# stm32_lora.net
KiCad netlist of a schematic drawn in EasyEDA Pro
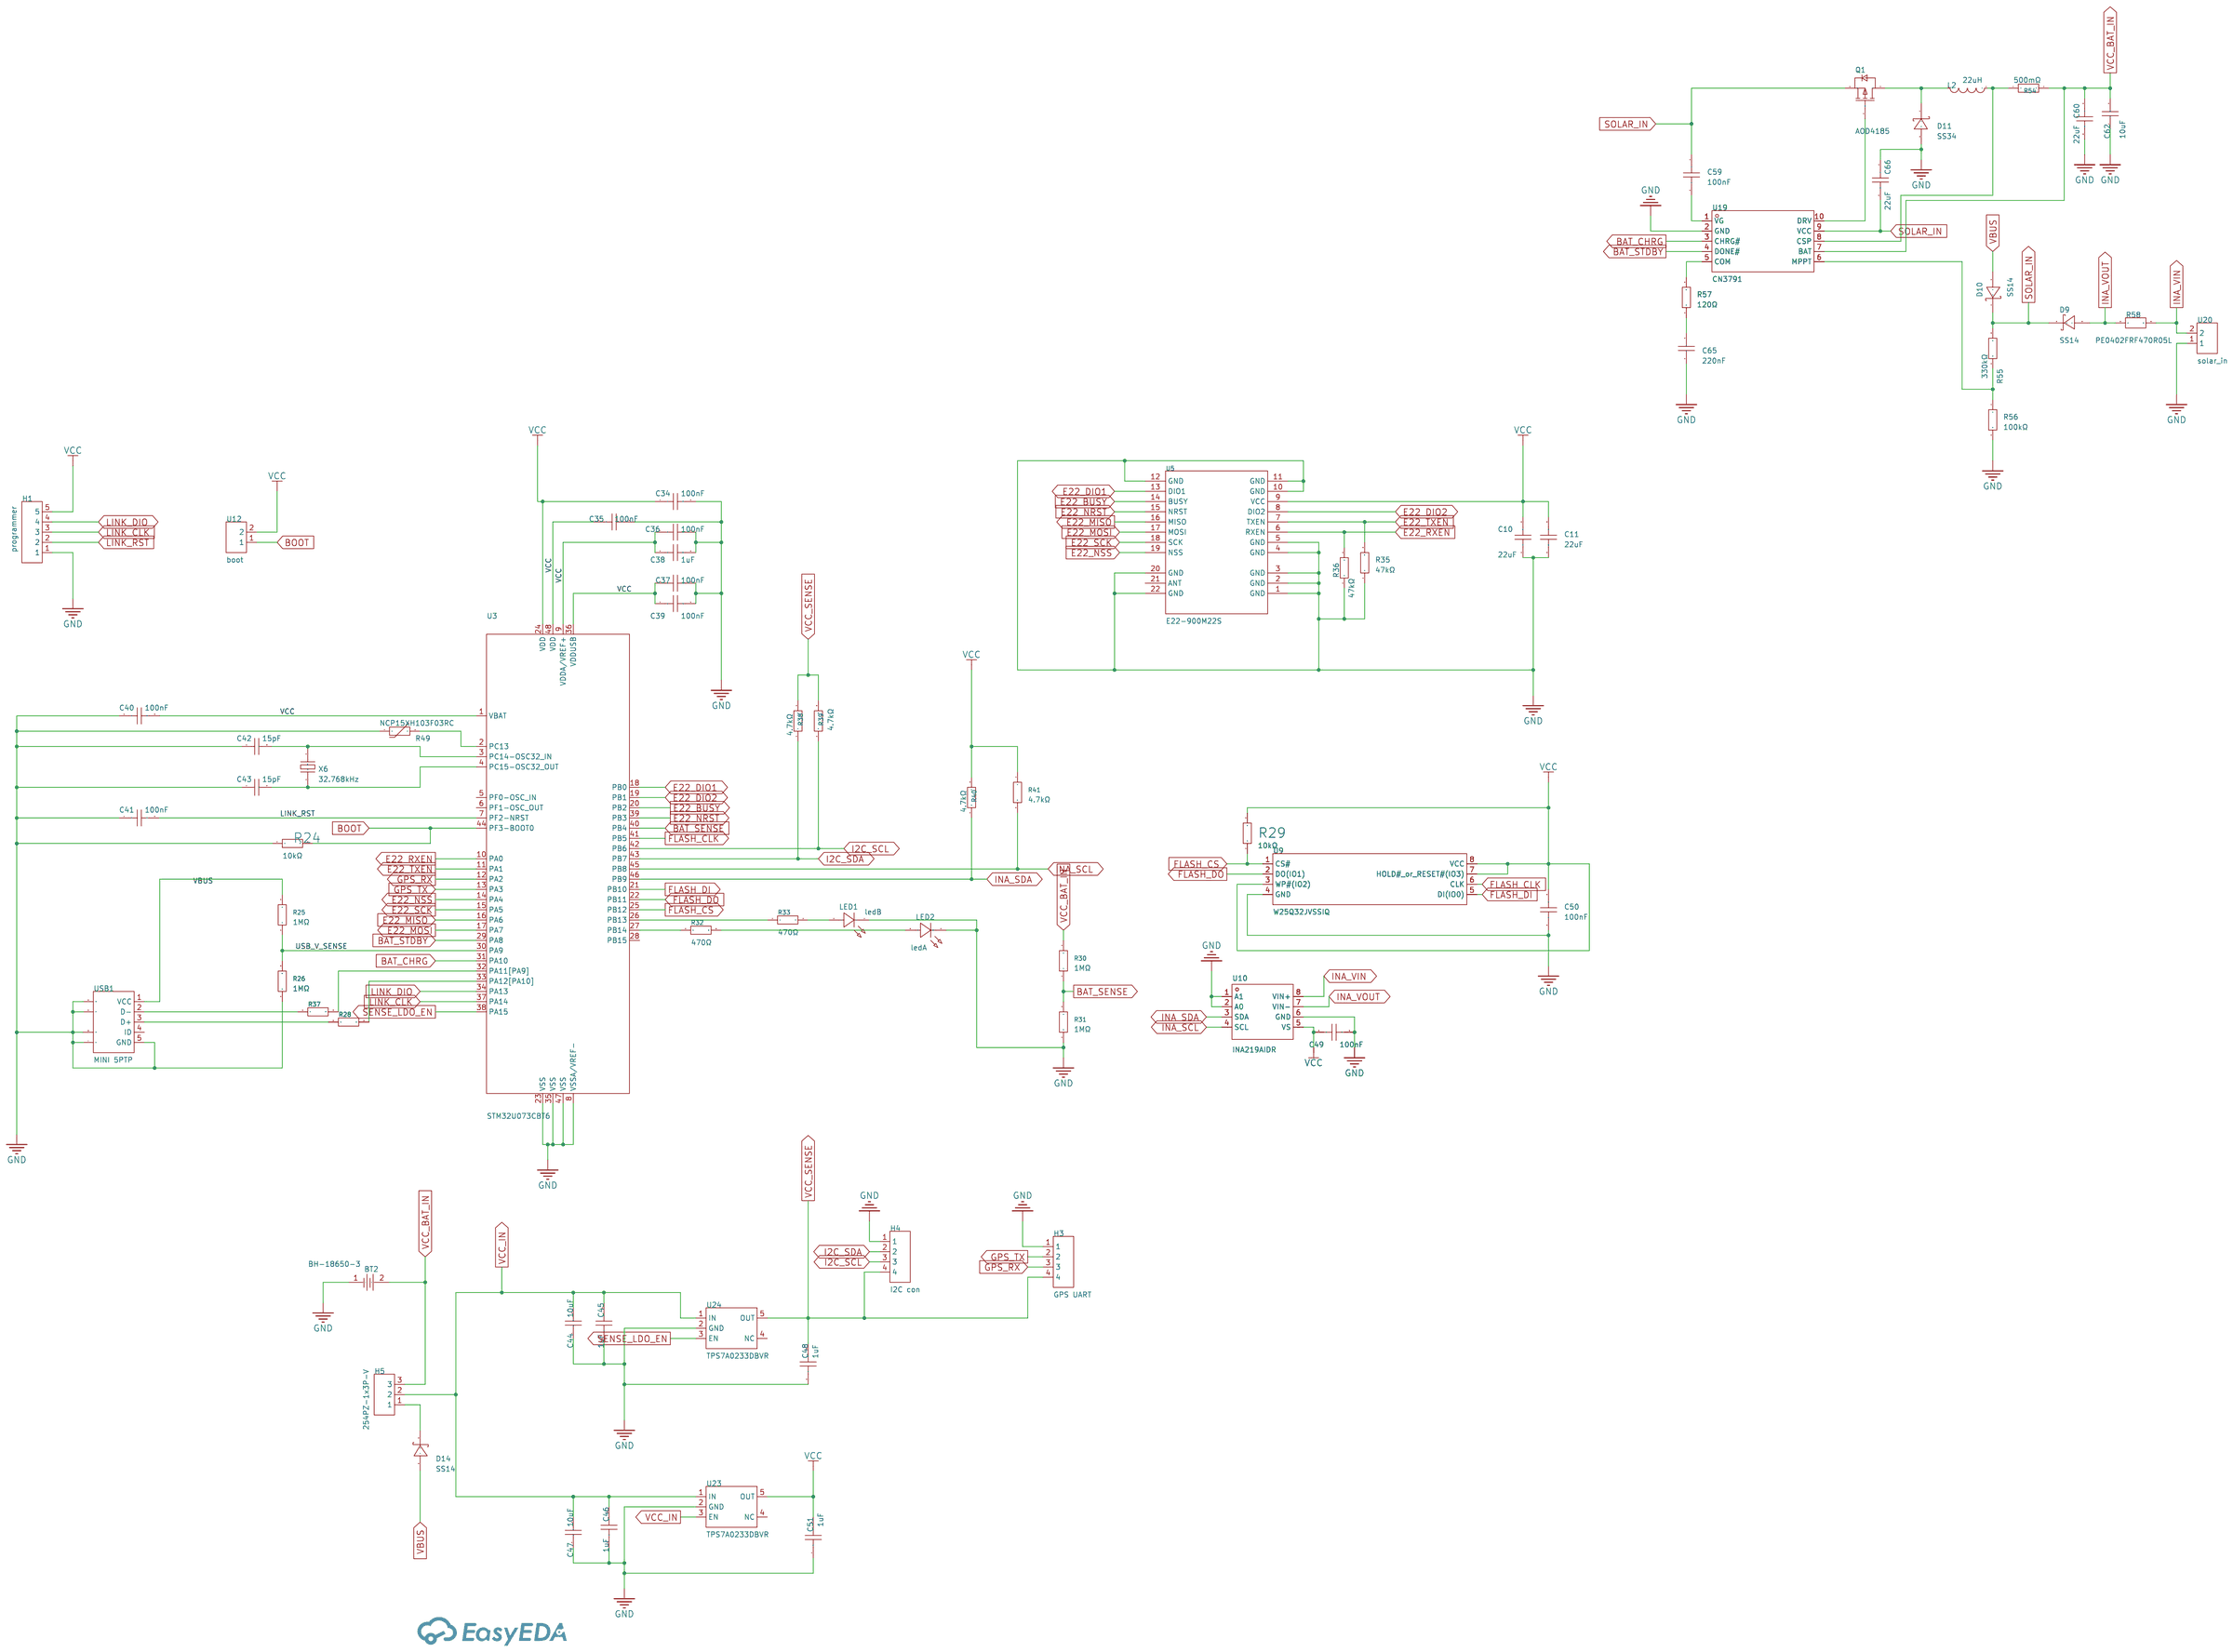
[diagram p0: schematic sheet]

(export (version "E")
  (design (tool "Eeschema 10.0.6"))
  (components
    (comp (ref "BT2")
      (value "BH-18650-3")
      (footprint "easyedapro:BAT-TH_BH-18650-3")
      (fields (field (name "Manufacturer") "HanElectricity(瀚源)"))
      (libsource (lib "easyedapro") (part "BH-18650-3"))
    )
    (comp (ref "C10")
      (value "22uF")
      (footprint "easyedapro:C0603")
      (description "Capacitance:22uF Tolerance:±20% Tolerance:±20% Voltage Rating:6.3V Temperature Coefficient:X5R")
      (fields
        (field (name "Manufacturer Part") "CL10A226MQ8NRNC")
        (field (name "Manufacturer") "SAMSUNG(三星)")
      )
      (libsource (lib "easyedapro") (part "CL10A226MQ8NRNC"))
    )
    (comp (ref "C11")
      (value "22uF")
      (footprint "easyedapro:C0603")
      (description "Capacitance:22uF Tolerance:±20% Tolerance:±20% Voltage Rating:6.3V Temperature Coefficient:X5R")
      (fields
        (field (name "Manufacturer Part") "CL10A226MQ8NRNC")
        (field (name "Manufacturer") "SAMSUNG(三星)")
      )
      (libsource (lib "easyedapro") (part "CL10A226MQ8NRNC"))
    )
    (comp (ref "C34")
      (value "100nF")
      (footprint "easyedapro:C0402")
      (description "Capacitance:100nF Tolerance:±10% Tolerance:±10% Voltage Rating:16V Temperature Coefficient:X7R")
      (fields
        (field (name "Manufacturer Part") "CL05B104KO5NNNC")
        (field (name "Manufacturer") "SAMSUNG(三星)")
      )
      (libsource (lib "easyedapro") (part "CL05B104KO5NNNC"))
    )
    (comp (ref "C35")
      (value "100nF")
      (footprint "easyedapro:C0402")
      (description "Capacitance:100nF Tolerance:±10% Tolerance:±10% Voltage Rating:16V Temperature Coefficient:X7R")
      (fields
        (field (name "Manufacturer Part") "CL05B104KO5NNNC")
        (field (name "Manufacturer") "SAMSUNG(三星)")
      )
      (libsource (lib "easyedapro") (part "CL05B104KO5NNNC"))
    )
    (comp (ref "C36")
      (value "100nF")
      (footprint "easyedapro:C0402")
      (description "Capacitance:100nF Tolerance:±10% Tolerance:±10% Voltage Rating:16V Temperature Coefficient:X7R")
      (fields
        (field (name "Manufacturer Part") "CL05B104KO5NNNC")
        (field (name "Manufacturer") "SAMSUNG(三星)")
      )
      (libsource (lib "easyedapro") (part "CL05B104KO5NNNC"))
    )
    (comp (ref "C37")
      (value "100nF")
      (footprint "easyedapro:C0402")
      (description "Capacitance:100nF Tolerance:±10% Tolerance:±10% Voltage Rating:16V Temperature Coefficient:X7R")
      (fields
        (field (name "Manufacturer Part") "CL05B104KO5NNNC")
        (field (name "Manufacturer") "SAMSUNG(三星)")
      )
      (libsource (lib "easyedapro") (part "CL05B104KO5NNNC"))
    )
    (comp (ref "C38")
      (value "1uF")
      (footprint "easyedapro:C0402")
      (description "Capacitance:1uF Tolerance:±10% Tolerance:±10% Voltage Rating:25V Temperature Coefficient:X5R")
      (fields
        (field (name "Manufacturer Part") "CL05A105KA5NQNC")
        (field (name "Manufacturer") "SAMSUNG(三星)")
      )
      (libsource (lib "easyedapro") (part "CL05A105KA5NQNC"))
    )
    (comp (ref "C39")
      (value "100nF")
      (footprint "easyedapro:C0402")
      (description "Capacitance:100nF Tolerance:±10% Tolerance:±10% Voltage Rating:16V Temperature Coefficient:X7R")
      (fields
        (field (name "Manufacturer Part") "CL05B104KO5NNNC")
        (field (name "Manufacturer") "SAMSUNG(三星)")
      )
      (libsource (lib "easyedapro") (part "CL05B104KO5NNNC"))
    )
    (comp (ref "C40")
      (value "100nF")
      (footprint "easyedapro:C0402")
      (description "Capacitance:100nF Tolerance:±10% Tolerance:±10% Voltage Rating:16V Temperature Coefficient:X7R")
      (fields
        (field (name "Manufacturer Part") "CL05B104KO5NNNC")
        (field (name "Manufacturer") "SAMSUNG(三星)")
      )
      (libsource (lib "easyedapro") (part "CL05B104KO5NNNC"))
    )
    (comp (ref "C41")
      (value "100nF")
      (footprint "easyedapro:C0402")
      (description "Capacitance:100nF Tolerance:±10% Tolerance:±10% Voltage Rating:16V Temperature Coefficient:X7R")
      (fields
        (field (name "Manufacturer Part") "CL05B104KO5NNNC")
        (field (name "Manufacturer") "SAMSUNG(三星)")
      )
      (libsource (lib "easyedapro") (part "CL05B104KO5NNNC"))
    )
    (comp (ref "C42")
      (value "15pF")
      (footprint "easyedapro:C0402")
      (description "Capacitance:15pF Tolerance:±5% Tolerance:±5% Voltage Rating:50V Temperature Coefficient:C0G")
      (fields (field (name "Manufacturer Part") "0402CG150J500NT") (field (name "Manufacturer") "FH(风华)"))
      (libsource (lib "easyedapro") (part "0402CG150J500NT"))
    )
    (comp (ref "C43")
      (value "15pF")
      (footprint "easyedapro:C0402")
      (description "Capacitance:15pF Tolerance:±5% Tolerance:±5% Voltage Rating:50V Temperature Coefficient:C0G")
      (fields (field (name "Manufacturer Part") "0402CG150J500NT") (field (name "Manufacturer") "FH(风华)"))
      (libsource (lib "easyedapro") (part "0402CG150J500NT"))
    )
    (comp (ref "C44")
      (value "10uF")
      (footprint "easyedapro:C0402")
      (description "Capacitance:10uF Tolerance:±20% Tolerance:±20% Voltage Rating:6.3V Temperature Coefficient:X5R")
      (fields
        (field (name "Manufacturer Part") "CL05A106MQ5NUNC")
        (field (name "Manufacturer") "SAMSUNG(三星)")
      )
      (libsource (lib "easyedapro") (part "CL05A106MQ5NUNC"))
    )
    (comp (ref "C45")
      (value "1uF")
      (footprint "easyedapro:C0402")
      (description "Capacitance:1uF Tolerance:±10% Tolerance:±10% Voltage Rating:25V Temperature Coefficient:X5R")
      (fields
        (field (name "Manufacturer Part") "CL05A105KA5NQNC")
        (field (name "Manufacturer") "SAMSUNG(三星)")
      )
      (libsource (lib "easyedapro") (part "CL05A105KA5NQNC"))
    )
    (comp (ref "C46")
      (value "1uF")
      (footprint "easyedapro:C0402")
      (description "Capacitance:1uF Tolerance:±10% Tolerance:±10% Voltage Rating:25V Temperature Coefficient:X5R")
      (fields
        (field (name "Manufacturer Part") "CL05A105KA5NQNC")
        (field (name "Manufacturer") "SAMSUNG(三星)")
      )
      (libsource (lib "easyedapro") (part "CL05A105KA5NQNC"))
    )
    (comp (ref "C47")
      (value "10uF")
      (footprint "easyedapro:C0402")
      (description "Capacitance:10uF Tolerance:±20% Tolerance:±20% Voltage Rating:6.3V Temperature Coefficient:X5R")
      (fields
        (field (name "Manufacturer Part") "CL05A106MQ5NUNC")
        (field (name "Manufacturer") "SAMSUNG(三星)")
      )
      (libsource (lib "easyedapro") (part "CL05A106MQ5NUNC"))
    )
    (comp (ref "C48")
      (value "1uF")
      (footprint "easyedapro:C0402")
      (description "Capacitance:1uF Tolerance:±10% Tolerance:±10% Voltage Rating:25V Temperature Coefficient:X5R")
      (fields
        (field (name "Manufacturer Part") "CL05A105KA5NQNC")
        (field (name "Manufacturer") "SAMSUNG(三星)")
      )
      (libsource (lib "easyedapro") (part "CL05A105KA5NQNC"))
    )
    (comp (ref "C49")
      (value "100nF")
      (footprint "easyedapro:C0402")
      (description "Capacitance:100nF Tolerance:±10% Tolerance:±10% Voltage Rating:16V Temperature Coefficient:X7R")
      (fields
        (field (name "Manufacturer Part") "CL05B104KO5NNNC")
        (field (name "Manufacturer") "SAMSUNG(三星)")
      )
      (libsource (lib "easyedapro") (part "CL05B104KO5NNNC"))
    )
    (comp (ref "C50")
      (value "100nF")
      (footprint "easyedapro:C0402")
      (description "Capacitance:100nF Tolerance:±10% Tolerance:±10% Voltage Rating:16V Temperature Coefficient:X7R")
      (fields
        (field (name "Manufacturer Part") "CL05B104KO5NNNC")
        (field (name "Manufacturer") "SAMSUNG(三星)")
      )
      (libsource (lib "easyedapro") (part "CL05B104KO5NNNC"))
    )
    (comp (ref "C51")
      (value "1uF")
      (footprint "easyedapro:C0402")
      (description "Capacitance:1uF Tolerance:±10% Tolerance:±10% Voltage Rating:25V Temperature Coefficient:X5R")
      (fields
        (field (name "Manufacturer Part") "CL05A105KA5NQNC")
        (field (name "Manufacturer") "SAMSUNG(三星)")
      )
      (libsource (lib "easyedapro") (part "CL05A105KA5NQNC"))
    )
    (comp (ref "C59")
      (value "100nF")
      (footprint "easyedapro:C0402")
      (description "Capacitance:100nF Tolerance:±10% Tolerance:±10% Voltage Rating:16V Temperature Coefficient:X7R")
      (fields
        (field (name "Manufacturer Part") "CL05B104KO5NNNC")
        (field (name "Manufacturer") "SAMSUNG(三星)")
      )
      (libsource (lib "easyedapro") (part "CL05B104KO5NNNC"))
    )
    (comp (ref "C60")
      (value "22uF")
      (footprint "easyedapro:C0603")
      (description "Capacitance:22uF Tolerance:±20% Tolerance:±20% Voltage Rating:6.3V Temperature Coefficient:X5R")
      (fields
        (field (name "Manufacturer Part") "CL10A226MQ8NRNC")
        (field (name "Manufacturer") "SAMSUNG(三星)")
      )
      (libsource (lib "easyedapro") (part "CL10A226MQ8NRNC"))
    )
    (comp (ref "C62")
      (value "10uF")
      (footprint "easyedapro:C0402")
      (description "Capacitance:10uF Tolerance:±20% Tolerance:±20% Voltage Rating:6.3V Temperature Coefficient:X5R")
      (fields
        (field (name "Manufacturer Part") "CL05A106MQ5NUNC")
        (field (name "Manufacturer") "SAMSUNG(三星)")
      )
      (libsource (lib "easyedapro") (part "CL05A106MQ5NUNC"))
    )
    (comp (ref "C65")
      (value "220nF")
      (footprint "easyedapro:C0402")
      (description "Capacitance:220nF Tolerance:±10% Tolerance:±10% Voltage Rating:16V Temperature Coefficient:X7R")
      (fields
        (field (name "Manufacturer Part") "CL05B224KO5NNNC")
        (field (name "Manufacturer") "SAMSUNG(三星)")
      )
      (libsource (lib "easyedapro") (part "CL05B224KO5NNNC"))
    )
    (comp (ref "C66")
      (value "22uF")
      (footprint "easyedapro:C0603")
      (description "Capacitance:22uF Tolerance:±20% Tolerance:±20% Voltage Rating:6.3V Temperature Coefficient:X5R")
      (fields
        (field (name "Manufacturer Part") "CL10A226MQ8NRNC")
        (field (name "Manufacturer") "SAMSUNG(三星)")
      )
      (libsource (lib "easyedapro") (part "CL10A226MQ8NRNC"))
    )
    (comp (ref "D9")
      (value "SS14")
      (footprint "easyedapro:SMA_L4.2-W2.6-LS5.0-RD_1")
      (fields (field (name "Manufacturer") "MDD(辰达半导体)"))
      (libsource (lib "easyedapro") (part "SS14"))
    )
    (comp (ref "D10")
      (value "SS14")
      (footprint "easyedapro:SMA_L4.2-W2.6-LS5.0-RD_1")
      (fields (field (name "Manufacturer") "MDD(辰达半导体)"))
      (libsource (lib "easyedapro") (part "SS14"))
    )
    (comp (ref "D11")
      (value "SS34")
      (footprint "easyedapro:SMA_L4.3-W2.6-LS5.2-RD")
      (fields (field (name "Manufacturer") "MDD(辰达半导体)"))
      (libsource (lib "easyedapro") (part "SS34_C8678"))
    )
    (comp (ref "D14")
      (value "SS14")
      (footprint "easyedapro:SMA_L4.2-W2.6-LS5.0-RD_1")
      (fields (field (name "Manufacturer") "MDD(辰达半导体)"))
      (libsource (lib "easyedapro") (part "SS14"))
    )
    (comp (ref "H1")
      (value "programmer")
      (footprint "easyedapro:HDR-TH_5P-P2.54-V-M")
      (fields (field (name "Manufacturer Part") "22284050") (field (name "Manufacturer") "MOLEX"))
      (libsource (lib "easyedapro") (part "22284050"))
    )
    (comp (ref "H3")
      (value "GPS UART")
      (footprint "easyedapro:HDR-TH_4P-HX-PH254-01-04-Z-L11.5")
      (fields
        (field (name "Manufacturer Part") "HX PH254-01-04-Z-L11.5 straight pin header")
        (field (name "Manufacturer") "hanxia(韩下)")
      )
      (libsource (lib "easyedapro") (part "HX PH254-01-04-Z-L11.5 STRAIGHT PIN HEADER"))
    )
    (comp (ref "H4")
      (value "I2C con")
      (footprint "easyedapro:HDR-TH_4P-HX-PH254-01-04-Z-L11.5")
      (fields
        (field (name "Manufacturer Part") "HX PH254-01-04-Z-L11.5 straight pin header")
        (field (name "Manufacturer") "hanxia(韩下)")
      )
      (libsource (lib "easyedapro") (part "HX PH254-01-04-Z-L11.5 STRAIGHT PIN HEADER"))
    )
    (comp (ref "H5")
      (value "254PZ-1x3P-V")
      (footprint "easyedapro:HDR-TH_3P-P2.54-V-M")
      (fields (field (name "Manufacturer") "LXWCONN(连兴旺电子)"))
      (libsource (lib "easyedapro") (part "254PZ-1X3P-V"))
    )
    (comp (ref "L2")
      (value "22uH")
      (footprint "easyedapro:IND-SMD_L4.0-W4.0_SLW4010S")
      (fields (field (name "Manufacturer Part") "SWPA4030S220MT") (field (name "Manufacturer") "Sunlord(顺络)"))
      (libsource (lib "easyedapro") (part "SWPA4030S220MT"))
    )
    (comp (ref "LED1")
      (value "ledB")
      (footprint "easyedapro:LED0603-RD")
      (fields
        (field (name "Manufacturer Part") "19-217/G7C-AM1N2B/6T")
        (field (name "Manufacturer") "EVERLIGHT(亿光)")
      )
      (libsource (lib "easyedapro") (part "19-217/G7C-AM1N2B/6T"))
    )
    (comp (ref "LED2")
      (value "ledA")
      (footprint "easyedapro:LED0603-RD")
      (fields
        (field (name "Manufacturer Part") "19-217/G7C-AM1N2B/6T")
        (field (name "Manufacturer") "EVERLIGHT(亿光)")
      )
      (libsource (lib "easyedapro") (part "19-217/G7C-AM1N2B/6T"))
    )
    (comp (ref "Q1")
      (value "AOD4185")
      (footprint "easyedapro:TO-252-3_L6.5-W5.8-P4.60-LS9.9-BR")
      (fields (field (name "Manufacturer") "HXY MOSFET(华轩阳电子)"))
      (libsource (lib "easyedapro") (part "AOD4185_C5261064"))
    )
    (comp (ref "R24")
      (value "10kΩ")
      (footprint "easyedapro:R0603")
      (fields
        (field (name "Manufacturer Part") "0603WAF1002T5E")
        (field (name "Manufacturer") "UNI-ROYAL(厚声)")
      )
      (libsource (lib "easyedapro") (part "0603WAF1002T5E"))
    )
    (comp (ref "R25")
      (value "1MΩ")
      (footprint "easyedapro:R0402")
      (fields
        (field (name "Manufacturer Part") "0402WGF1004TCE")
        (field (name "Manufacturer") "UNI-ROYAL(厚声)")
      )
      (libsource (lib "easyedapro") (part "0402WGF1004TCE"))
    )
    (comp (ref "R26")
      (value "1MΩ")
      (footprint "easyedapro:R0402")
      (fields
        (field (name "Manufacturer Part") "0402WGF1004TCE")
        (field (name "Manufacturer") "UNI-ROYAL(厚声)")
      )
      (libsource (lib "easyedapro") (part "0402WGF1004TCE"))
    )
    (comp (ref "R28")
      (value "22Ω")
      (footprint "easyedapro:R0402")
      (fields
        (field (name "Manufacturer Part") "0402WGF220JTCE")
        (field (name "Manufacturer") "UNI-ROYAL(厚声)")
      )
      (libsource (lib "easyedapro") (part "0402WGF220JTCE"))
    )
    (comp (ref "R29")
      (value "10kΩ")
      (footprint "easyedapro:R0603")
      (fields
        (field (name "Manufacturer Part") "0603WAF1002T5E")
        (field (name "Manufacturer") "UNI-ROYAL(厚声)")
      )
      (libsource (lib "easyedapro") (part "0603WAF1002T5E"))
    )
    (comp (ref "R30")
      (value "1MΩ")
      (footprint "easyedapro:R0402")
      (fields
        (field (name "Manufacturer Part") "0402WGF1004TCE")
        (field (name "Manufacturer") "UNI-ROYAL(厚声)")
      )
      (libsource (lib "easyedapro") (part "0402WGF1004TCE"))
    )
    (comp (ref "R31")
      (value "1MΩ")
      (footprint "easyedapro:R0402")
      (fields
        (field (name "Manufacturer Part") "0402WGF1004TCE")
        (field (name "Manufacturer") "UNI-ROYAL(厚声)")
      )
      (libsource (lib "easyedapro") (part "0402WGF1004TCE"))
    )
    (comp (ref "R32")
      (value "470Ω")
      (footprint "easyedapro:R0402")
      (fields
        (field (name "Manufacturer Part") "0402WGF4700TCE")
        (field (name "Manufacturer") "UNI-ROYAL(厚声)")
      )
      (libsource (lib "easyedapro") (part "0402WGF4700TCE"))
    )
    (comp (ref "R33")
      (value "470Ω")
      (footprint "easyedapro:R0402")
      (fields
        (field (name "Manufacturer Part") "0402WGF4700TCE")
        (field (name "Manufacturer") "UNI-ROYAL(厚声)")
      )
      (libsource (lib "easyedapro") (part "0402WGF4700TCE"))
    )
    (comp (ref "R35")
      (value "47kΩ")
      (footprint "easyedapro:R0402")
      (fields
        (field (name "Manufacturer Part") "0402WGF4702TCE")
        (field (name "Manufacturer") "UNI-ROYAL(厚声)")
      )
      (libsource (lib "easyedapro") (part "0402WGF4702TCE"))
    )
    (comp (ref "R36")
      (value "47kΩ")
      (footprint "easyedapro:R0402")
      (fields
        (field (name "Manufacturer Part") "0402WGF4702TCE")
        (field (name "Manufacturer") "UNI-ROYAL(厚声)")
      )
      (libsource (lib "easyedapro") (part "0402WGF4702TCE"))
    )
    (comp (ref "R37")
      (value "22Ω")
      (footprint "easyedapro:R0402")
      (fields
        (field (name "Manufacturer Part") "0402WGF220JTCE")
        (field (name "Manufacturer") "UNI-ROYAL(厚声)")
      )
      (libsource (lib "easyedapro") (part "0402WGF220JTCE"))
    )
    (comp (ref "R38")
      (value "4.7kΩ")
      (footprint "easyedapro:R0402")
      (fields
        (field (name "Manufacturer Part") "0402WGF4701TCE")
        (field (name "Manufacturer") "UNI-ROYAL(厚声)")
      )
      (libsource (lib "easyedapro") (part "0402WGF4701TCE"))
    )
    (comp (ref "R39")
      (value "4.7kΩ")
      (footprint "easyedapro:R0402")
      (fields
        (field (name "Manufacturer Part") "0402WGF4701TCE")
        (field (name "Manufacturer") "UNI-ROYAL(厚声)")
      )
      (libsource (lib "easyedapro") (part "0402WGF4701TCE"))
    )
    (comp (ref "R40")
      (value "4.7kΩ")
      (footprint "easyedapro:R0402")
      (fields
        (field (name "Manufacturer Part") "0402WGF4701TCE")
        (field (name "Manufacturer") "UNI-ROYAL(厚声)")
      )
      (libsource (lib "easyedapro") (part "0402WGF4701TCE"))
    )
    (comp (ref "R41")
      (value "4.7kΩ")
      (footprint "easyedapro:R0402")
      (fields
        (field (name "Manufacturer Part") "0402WGF4701TCE")
        (field (name "Manufacturer") "UNI-ROYAL(厚声)")
      )
      (libsource (lib "easyedapro") (part "0402WGF4701TCE"))
    )
    (comp (ref "R49")
      (value "NCP15XH103F03RC")
      (footprint "easyedapro:R0402")
      (fields (field (name "Manufacturer") "muRata(村田)"))
      (libsource (lib "easyedapro") (part "NCP15XH103F03RC"))
    )
    (comp (ref "R54")
      (value "500mΩ")
      (footprint "easyedapro:R0805")
      (fields
        (field (name "Manufacturer Part") "0805W8F500LT5E")
        (field (name "Manufacturer") "UNI-ROYAL(厚声)")
      )
      (libsource (lib "easyedapro") (part "0805W8F500LT5E"))
    )
    (comp (ref "R55")
      (value "330kΩ")
      (footprint "easyedapro:R0603")
      (fields
        (field (name "Manufacturer Part") "0603WAF3303T5E")
        (field (name "Manufacturer") "UNI-ROYAL(厚声)")
      )
      (libsource (lib "easyedapro") (part "0603WAF3303T5E"))
    )
    (comp (ref "R56")
      (value "100kΩ")
      (footprint "easyedapro:R0603")
      (fields
        (field (name "Manufacturer Part") "0603WAF1003T5E")
        (field (name "Manufacturer") "UNI-ROYAL(厚声)")
      )
      (libsource (lib "easyedapro") (part "0603WAF1003T5E"))
    )
    (comp (ref "R57")
      (value "120Ω")
      (footprint "easyedapro:R0402")
      (fields
        (field (name "Manufacturer Part") "0402WGF1200TCE")
        (field (name "Manufacturer") "UNI-ROYAL(厚声)")
      )
      (libsource (lib "easyedapro") (part "0402WGF1200TCE"))
    )
    (comp (ref "R58")
      (value "PE0402FRF470R05L")
      (footprint "easyedapro:R0402")
      (fields (field (name "Manufacturer") "YAGEO(国巨)"))
      (libsource (lib "easyedapro") (part "PE0402FRF470R05L"))
    )
    (comp (ref "U3")
      (value "STM32U073CBT6")
      (footprint "easyedapro:LFQFP-48_L7.0-W7.0-P0.50-LS9.0-BL")
      (fields (field (name "Manufacturer") "ST(意法半导体)"))
      (libsource (lib "easyedapro") (part "STM32U073CBT6"))
    )
    (comp (ref "U5")
      (value "E22-900M22S")
      (footprint "easyedapro:WIRELM-SMD_E22-900M22S")
      (fields (field (name "Manufacturer") "EBYTE(亿佰特)"))
      (libsource (lib "easyedapro") (part "E22-900M22S"))
    )
    (comp (ref "U9")
      (value "W25Q32JVSSIQ")
      (footprint "easyedapro:SOIC-8_L5.3-W5.3-P1.27-LS8.0-BL")
      (fields (field (name "Manufacturer") "Winbond(华邦)"))
      (libsource (lib "easyedapro") (part "W25Q32JVSSIQ_C179173"))
    )
    (comp (ref "U10")
      (value "INA219AIDR")
      (footprint "easyedapro:SOIC-8_L4.9-W3.9-P1.27-LS6.0-BL")
      (fields (field (name "Manufacturer") "TI(德州仪器)"))
      (libsource (lib "easyedapro") (part "INA219AIDR"))
    )
    (comp (ref "U12")
      (value "boot")
      (footprint "easyedapro:CONN-TH_HC-PZ254-11.5L-1X2PZ")
      (fields
        (field (name "Manufacturer Part") "HC-PZ254-11.5L-1x2PZ")
        (field (name "Manufacturer") "HC(虹成电子)")
      )
      (libsource (lib "easyedapro") (part "HC-PZ254-11.5L-1X2PZ"))
    )
    (comp (ref "U19")
      (value "CN3791")
      (footprint "easyedapro:SSOP-10_L4.9-W3.9-P1.00-LS6.0-BL")
      (fields (field (name "Manufacturer") "CONSONANCE(上海如韵)"))
      (libsource (lib "easyedapro") (part "CN3791"))
    )
    (comp (ref "U20")
      (value "solar_in")
      (footprint "easyedapro:CONN-TH_HC-PZ254-11.5L-1X2PZ")
      (fields
        (field (name "Manufacturer Part") "HC-PZ254-11.5L-1x2PZ")
        (field (name "Manufacturer") "HC(虹成电子)")
      )
      (libsource (lib "easyedapro") (part "HC-PZ254-11.5L-1X2PZ"))
    )
    (comp (ref "U23")
      (value "TPS7A0233DBVR")
      (footprint "easyedapro:SOT-23-5_L2.9-W1.6-P0.95-LS2.8-BL")
      (fields (field (name "Manufacturer") "TI(德州仪器)"))
      (libsource (lib "easyedapro") (part "TPS7A0233DBVR"))
    )
    (comp (ref "U24")
      (value "TPS7A0233DBVR")
      (footprint "easyedapro:SOT-23-5_L2.9-W1.6-P0.95-LS2.8-BL")
      (fields (field (name "Manufacturer") "TI(德州仪器)"))
      (libsource (lib "easyedapro") (part "TPS7A0233DBVR"))
    )
    (comp (ref "USB1")
      (value "MINI 5PTP")
      (footprint "easyedapro:MINI-USB-SMD_MINI-5PTP")
      (fields (field (name "Manufacturer") "SHOU HAN(首韩)"))
      (libsource (lib "easyedapro") (part "MINI 5PTP"))
    )
    (comp (ref "X6")
      (value "32.768kHz")
      (footprint "easyedapro:CRYSTAL-SMD_L3.2-W1.5-1")
      (fields
        (field (name "Manufacturer Part") "FC-135R 32.7680KA-A3")
        (field (name "Manufacturer") "EPSON(爱普生)")
      )
      (libsource (lib "easyedapro") (part "FC-135R 32.7680KA-A3"))
    )
  )
  (nets
    (net (code "1") (name "/USB_V_SENSE") (class "Default")
      (node (ref "R25") (pin "1") (pinfunction "1_1") (pintype "input"))
      (node (ref "R26") (pin "2") (pinfunction "2_2") (pintype "input"))
      (node (ref "U3") (pin "30") (pinfunction "PA9_30") (pintype "unspecified"))
    )
    (net (code "2") (name "BAT_CHRG") (class "Default")
      (node (ref "U19") (pin "3") (pinfunction "CHRG#_3") (pintype "unspecified"))
      (node (ref "U3") (pin "31") (pinfunction "PA10_31") (pintype "unspecified"))
    )
    (net (code "3") (name "BAT_SENSE") (class "Default")
      (node (ref "R30") (pin "1") (pinfunction "1_1") (pintype "input"))
      (node (ref "R31") (pin "2") (pinfunction "2_2") (pintype "input"))
      (node (ref "U3") (pin "40") (pinfunction "PB4_40") (pintype "unspecified"))
    )
    (net (code "4") (name "BAT_STDBY") (class "Default")
      (node (ref "U19") (pin "4") (pinfunction "DONE#_4") (pintype "unspecified"))
      (node (ref "U3") (pin "29") (pinfunction "PA8_29") (pintype "unspecified"))
    )
    (net (code "5") (name "BOOT") (class "Default")
      (node (ref "R24") (pin "2") (pinfunction "2_2") (pintype "input"))
      (node (ref "U12") (pin "1") (pinfunction "1_1") (pintype "unspecified"))
      (node (ref "U3") (pin "44") (pinfunction "PF3-BOOT0_44") (pintype "unspecified"))
    )
    (net (code "6") (name "E22_BUSY") (class "Default")
      (node (ref "U3") (pin "20") (pinfunction "PB2_20") (pintype "unspecified"))
      (node (ref "U5") (pin "14") (pinfunction "BUSY_14") (pintype "input"))
    )
    (net (code "7") (name "E22_DIO1") (class "Default")
      (node (ref "U3") (pin "18") (pinfunction "PB0_18") (pintype "unspecified"))
      (node (ref "U5") (pin "13") (pinfunction "DIO1_13") (pintype "input"))
    )
    (net (code "8") (name "E22_DIO2") (class "Default")
      (node (ref "U3") (pin "19") (pinfunction "PB1_19") (pintype "unspecified"))
      (node (ref "U5") (pin "8") (pinfunction "DIO2_8") (pintype "input"))
    )
    (net (code "9") (name "E22_MISO") (class "Default")
      (node (ref "U3") (pin "16") (pinfunction "PA6_16") (pintype "unspecified"))
      (node (ref "U5") (pin "16") (pinfunction "MISO_16") (pintype "input"))
    )
    (net (code "10") (name "E22_MOSI") (class "Default")
      (node (ref "U3") (pin "17") (pinfunction "PA7_17") (pintype "unspecified"))
      (node (ref "U5") (pin "17") (pinfunction "MOSI_17") (pintype "input"))
    )
    (net (code "11") (name "E22_NRST") (class "Default")
      (node (ref "U3") (pin "39") (pinfunction "PB3_39") (pintype "unspecified"))
      (node (ref "U5") (pin "15") (pinfunction "NRST_15") (pintype "input"))
    )
    (net (code "12") (name "E22_NSS") (class "Default")
      (node (ref "U3") (pin "14") (pinfunction "PA4_14") (pintype "unspecified"))
      (node (ref "U5") (pin "19") (pinfunction "NSS_19") (pintype "input"))
    )
    (net (code "13") (name "E22_RXEN") (class "Default")
      (node (ref "R36") (pin "2") (pinfunction "2_2") (pintype "input"))
      (node (ref "U3") (pin "10") (pinfunction "PA0_10") (pintype "unspecified"))
      (node (ref "U5") (pin "6") (pinfunction "RXEN_6") (pintype "input"))
    )
    (net (code "14") (name "E22_SCK") (class "Default")
      (node (ref "U3") (pin "15") (pinfunction "PA5_15") (pintype "unspecified"))
      (node (ref "U5") (pin "18") (pinfunction "SCK_18") (pintype "input"))
    )
    (net (code "15") (name "E22_TXEN") (class "Default")
      (node (ref "R35") (pin "2") (pinfunction "2_2") (pintype "input"))
      (node (ref "U3") (pin "11") (pinfunction "PA1_11") (pintype "unspecified"))
      (node (ref "U5") (pin "7") (pinfunction "TXEN_7") (pintype "input"))
    )
    (net (code "16") (name "FLASH_CLK") (class "Default")
      (node (ref "U3") (pin "41") (pinfunction "PB5_41") (pintype "unspecified"))
      (node (ref "U9") (pin "6") (pinfunction "CLK_6") (pintype "unspecified"))
    )
    (net (code "17") (name "FLASH_CS") (class "Default")
      (node (ref "R29") (pin "1") (pinfunction "1_1") (pintype "input"))
      (node (ref "U3") (pin "25") (pinfunction "PB12_25") (pintype "unspecified"))
      (node (ref "U9") (pin "1") (pinfunction "CS#_1") (pintype "unspecified"))
    )
    (net (code "18") (name "FLASH_DI") (class "Default")
      (node (ref "U3") (pin "21") (pinfunction "PB10_21") (pintype "unspecified"))
      (node (ref "U9") (pin "5") (pinfunction "DI(IO0)_5") (pintype "unspecified"))
    )
    (net (code "19") (name "FLASH_DO") (class "Default")
      (node (ref "U3") (pin "22") (pinfunction "PB11_22") (pintype "unspecified"))
      (node (ref "U9") (pin "2") (pinfunction "DO(IO1)_2") (pintype "unspecified"))
    )
    (net (code "20") (name "GND") (class "Default")
      (node (ref "BT2") (pin "1") (pinfunction "-_1") (pintype "input"))
      (node (ref "C10") (pin "1") (pinfunction "1_1") (pintype "unspecified"))
      (node (ref "C11") (pin "1") (pinfunction "1_1") (pintype "unspecified"))
      (node (ref "C34") (pin "2") (pinfunction "2_2") (pintype "unspecified"))
      (node (ref "C35") (pin "2") (pinfunction "2_2") (pintype "unspecified"))
      (node (ref "C36") (pin "2") (pinfunction "2_2") (pintype "unspecified"))
      (node (ref "C37") (pin "2") (pinfunction "2_2") (pintype "unspecified"))
      (node (ref "C38") (pin "2") (pinfunction "2_2") (pintype "unspecified"))
      (node (ref "C39") (pin "2") (pinfunction "2_2") (pintype "unspecified"))
      (node (ref "C40") (pin "1") (pinfunction "1_1") (pintype "unspecified"))
      (node (ref "C41") (pin "1") (pinfunction "1_1") (pintype "unspecified"))
      (node (ref "C42") (pin "1") (pinfunction "1_1") (pintype "input"))
      (node (ref "C43") (pin "1") (pinfunction "1_1") (pintype "input"))
      (node (ref "C44") (pin "1") (pinfunction "1_1") (pintype "input"))
      (node (ref "C45") (pin "1") (pinfunction "1_1") (pintype "unspecified"))
      (node (ref "C46") (pin "1") (pinfunction "1_1") (pintype "unspecified"))
      (node (ref "C47") (pin "1") (pinfunction "1_1") (pintype "input"))
      (node (ref "C48") (pin "1") (pinfunction "1_1") (pintype "unspecified"))
      (node (ref "C49") (pin "2") (pinfunction "2_2") (pintype "unspecified"))
      (node (ref "C50") (pin "1") (pinfunction "1_1") (pintype "unspecified"))
      (node (ref "C51") (pin "1") (pinfunction "1_1") (pintype "unspecified"))
      (node (ref "C60") (pin "2") (pinfunction "2_2") (pintype "unspecified"))
      (node (ref "C62") (pin "1") (pinfunction "1_1") (pintype "input"))
      (node (ref "C65") (pin "1") (pinfunction "1_1") (pintype "input"))
      (node (ref "C66") (pin "1") (pinfunction "1_1") (pintype "unspecified"))
      (node (ref "D11") (pin "2") (pinfunction "A_2") (pintype "unspecified"))
      (node (ref "H1") (pin "1") (pinfunction "1_1") (pintype "unspecified"))
      (node (ref "H3") (pin "1") (pinfunction "1_1") (pintype "unspecified"))
      (node (ref "H4") (pin "1") (pinfunction "1_1") (pintype "unspecified"))
      (node (ref "LED1") (pin "1") (pinfunction "K_1") (pintype "unspecified"))
      (node (ref "LED2") (pin "1") (pinfunction "K_1") (pintype "unspecified"))
      (node (ref "R24") (pin "1") (pinfunction "1_1") (pintype "input"))
      (node (ref "R26") (pin "1") (pinfunction "1_1") (pintype "input"))
      (node (ref "R31") (pin "1") (pinfunction "1_1") (pintype "input"))
      (node (ref "R35") (pin "1") (pinfunction "1_1") (pintype "input"))
      (node (ref "R36") (pin "1") (pinfunction "1_1") (pintype "input"))
      (node (ref "R49") (pin "1") (pinfunction "1_1") (pintype "input"))
      (node (ref "R56") (pin "2") (pinfunction "2_2") (pintype "input"))
      (node (ref "U10") (pin "1") (pinfunction "A1_1") (pintype "unspecified"))
      (node (ref "U10") (pin "2") (pinfunction "A0_2") (pintype "unspecified"))
      (node (ref "U10") (pin "6") (pinfunction "GND_6") (pintype "unspecified"))
      (node (ref "U19") (pin "2") (pinfunction "GND_2") (pintype "unspecified"))
      (node (ref "U20") (pin "1") (pinfunction "1_1") (pintype "unspecified"))
      (node (ref "U23") (pin "2") (pinfunction "GND_2") (pintype "unspecified"))
      (node (ref "U24") (pin "2") (pinfunction "GND_2") (pintype "unspecified"))
      (node (ref "U3") (pin "23") (pinfunction "VSS_23") (pintype "unspecified"))
      (node (ref "U3") (pin "35") (pinfunction "VSS_35") (pintype "unspecified"))
      (node (ref "U3") (pin "47") (pinfunction "VSS_47") (pintype "unspecified"))
      (node (ref "U3") (pin "8") (pinfunction "VSSA/VREF-_8") (pintype "unspecified"))
      (node (ref "U5") (pin "1") (pinfunction "GND_1") (pintype "input"))
      (node (ref "U5") (pin "10") (pinfunction "GND_10") (pintype "input"))
      (node (ref "U5") (pin "11") (pinfunction "GND_11") (pintype "input"))
      (node (ref "U5") (pin "12") (pinfunction "GND_12") (pintype "input"))
      (node (ref "U5") (pin "2") (pinfunction "GND_2") (pintype "input"))
      (node (ref "U5") (pin "20") (pinfunction "GND_20") (pintype "input"))
      (node (ref "U5") (pin "22") (pinfunction "GND_22") (pintype "input"))
      (node (ref "U5") (pin "3") (pinfunction "GND_3") (pintype "input"))
      (node (ref "U5") (pin "4") (pinfunction "GND_4") (pintype "input"))
      (node (ref "U5") (pin "5") (pinfunction "GND_5") (pintype "input"))
      (node (ref "U9") (pin "4") (pinfunction "GND_4") (pintype "unspecified"))
      (node (ref "USB1") (pin "5") (pinfunction "GND_5") (pintype "input"))
      (node (ref "USB1") (pin "6") (pinfunction "EH_6") (pintype "unspecified"))
      (node (ref "USB1") (pin "7") (pinfunction "EH_7") (pintype "unspecified"))
      (node (ref "USB1") (pin "8") (pinfunction "EH_8") (pintype "unspecified"))
      (node (ref "USB1") (pin "9") (pinfunction "EH_9") (pintype "unspecified"))
    )
    (net (code "21") (name "GPS_RX") (class "Default")
      (node (ref "H3") (pin "3") (pinfunction "3_3") (pintype "unspecified"))
      (node (ref "U3") (pin "12") (pinfunction "PA2_12") (pintype "unspecified"))
    )
    (net (code "22") (name "GPS_TX") (class "Default")
      (node (ref "H3") (pin "2") (pinfunction "2_2") (pintype "unspecified"))
      (node (ref "U3") (pin "13") (pinfunction "PA3_13") (pintype "unspecified"))
    )
    (net (code "23") (name "I2C_SCL") (class "Default")
      (node (ref "H4") (pin "3") (pinfunction "3_3") (pintype "unspecified"))
      (node (ref "R39") (pin "1") (pinfunction "1_1") (pintype "input"))
      (node (ref "U3") (pin "42") (pinfunction "PB6_42") (pintype "unspecified"))
    )
    (net (code "24") (name "I2C_SDA") (class "Default")
      (node (ref "H4") (pin "2") (pinfunction "2_2") (pintype "unspecified"))
      (node (ref "R38") (pin "1") (pinfunction "1_1") (pintype "input"))
      (node (ref "U3") (pin "43") (pinfunction "PB7_43") (pintype "unspecified"))
    )
    (net (code "25") (name "INA_SCL") (class "Default")
      (node (ref "R41") (pin "2") (pinfunction "2_2") (pintype "input"))
      (node (ref "U10") (pin "4") (pinfunction "SCL_4") (pintype "unspecified"))
      (node (ref "U3") (pin "45") (pinfunction "PB8_45") (pintype "unspecified"))
    )
    (net (code "26") (name "INA_SDA") (class "Default")
      (node (ref "R40") (pin "1") (pinfunction "1_1") (pintype "input"))
      (node (ref "U10") (pin "3") (pinfunction "SDA_3") (pintype "unspecified"))
      (node (ref "U3") (pin "46") (pinfunction "PB9_46") (pintype "unspecified"))
    )
    (net (code "27") (name "INA_VIN") (class "Default")
      (node (ref "R58") (pin "2") (pinfunction "2_2") (pintype "unspecified"))
      (node (ref "U10") (pin "8") (pinfunction "VIN+_8") (pintype "unspecified"))
      (node (ref "U20") (pin "2") (pinfunction "2_2") (pintype "unspecified"))
    )
    (net (code "28") (name "INA_VOUT") (class "Default")
      (node (ref "D9") (pin "2") (pinfunction "A_2") (pintype "unspecified"))
      (node (ref "R58") (pin "1") (pinfunction "1_1") (pintype "unspecified"))
      (node (ref "U10") (pin "7") (pinfunction "VIN-_7") (pintype "unspecified"))
    )
    (net (code "29") (name "LINK_CLK") (class "Default")
      (node (ref "H1") (pin "3") (pinfunction "3_3") (pintype "unspecified"))
      (node (ref "U3") (pin "37") (pinfunction "PA14_37") (pintype "unspecified"))
    )
    (net (code "30") (name "LINK_DIO") (class "Default")
      (node (ref "H1") (pin "4") (pinfunction "4_4") (pintype "unspecified"))
      (node (ref "U3") (pin "34") (pinfunction "PA13_34") (pintype "unspecified"))
    )
    (net (code "31") (name "LINK_RST") (class "Default")
      (node (ref "C41") (pin "2") (pinfunction "2_2") (pintype "unspecified"))
      (node (ref "H1") (pin "2") (pinfunction "2_2") (pintype "unspecified"))
      (node (ref "U3") (pin "7") (pinfunction "PF2-NRST_7") (pintype "unspecified"))
    )
    (net (code "32") (name "Net-(C65-Pad2)") (class "Default")
      (node (ref "C65") (pin "2") (pinfunction "2_2") (pintype "input"))
      (node (ref "R57") (pin "1") (pinfunction "1_1") (pintype "input"))
    )
    (net (code "33") (name "Net-(D11-K)") (class "Default")
      (node (ref "D11") (pin "1") (pinfunction "K_1") (pintype "unspecified"))
      (node (ref "L2") (pin "2") (pinfunction "2_2") (pintype "input"))
      (node (ref "Q1") (pin "2") (pinfunction "D_2") (pintype "unspecified"))
    )
    (net (code "34") (name "Net-(D14-K)") (class "Default")
      (node (ref "D14") (pin "1") (pinfunction "K_1") (pintype "unspecified"))
      (node (ref "H5") (pin "1") (pinfunction "1_1") (pintype "unspecified"))
    )
    (net (code "35") (name "Net-(LED1-A)") (class "Default")
      (node (ref "LED1") (pin "2") (pinfunction "A_2") (pintype "unspecified"))
      (node (ref "R33") (pin "2") (pinfunction "2_2") (pintype "input"))
    )
    (net (code "36") (name "Net-(LED2-A)") (class "Default")
      (node (ref "LED2") (pin "2") (pinfunction "A_2") (pintype "unspecified"))
      (node (ref "R32") (pin "2") (pinfunction "2_2") (pintype "input"))
    )
    (net (code "37") (name "Net-(Q1-G)") (class "Default")
      (node (ref "Q1") (pin "1") (pinfunction "G_1") (pintype "unspecified"))
      (node (ref "U19") (pin "10") (pinfunction "DRV_10") (pintype "unspecified"))
    )
    (net (code "38") (name "Net-(U3-PA11[PA9])") (class "Default")
      (node (ref "R37") (pin "2") (pinfunction "2_2") (pintype "input"))
      (node (ref "U3") (pin "32") (pinfunction "PA11[PA9]_32") (pintype "unspecified"))
    )
    (net (code "39") (name "Net-(U3-PA12[PA10])") (class "Default")
      (node (ref "R28") (pin "2") (pinfunction "2_2") (pintype "input"))
      (node (ref "U3") (pin "33") (pinfunction "PA12[PA10]_33") (pintype "unspecified"))
    )
    (net (code "40") (name "Net-(U3-PB13)") (class "Default")
      (node (ref "R33") (pin "1") (pinfunction "1_1") (pintype "input"))
      (node (ref "U3") (pin "26") (pinfunction "PB13_26") (pintype "unspecified"))
    )
    (net (code "41") (name "Net-(U3-PB14)") (class "Default")
      (node (ref "R32") (pin "1") (pinfunction "1_1") (pintype "input"))
      (node (ref "U3") (pin "27") (pinfunction "PB14_27") (pintype "unspecified"))
    )
    (net (code "42") (name "Net-(U3-PC13)") (class "Default")
      (node (ref "R49") (pin "2") (pinfunction "2_2") (pintype "input"))
      (node (ref "U3") (pin "2") (pinfunction "PC13_2") (pintype "unspecified"))
    )
    (net (code "43") (name "Net-(U3-PC14-OSC32_IN)") (class "Default")
      (node (ref "C42") (pin "2") (pinfunction "2_2") (pintype "input"))
      (node (ref "U3") (pin "3") (pinfunction "PC14-OSC32_IN_3") (pintype "unspecified"))
      (node (ref "X6") (pin "2") (pinfunction "GND_2") (pintype "input"))
    )
    (net (code "44") (name "Net-(U3-PC15-OSC32_OUT)") (class "Default")
      (node (ref "C43") (pin "2") (pinfunction "2_2") (pintype "input"))
      (node (ref "U3") (pin "4") (pinfunction "PC15-OSC32_OUT_4") (pintype "unspecified"))
      (node (ref "X6") (pin "1") (pinfunction "1_1") (pintype "input"))
    )
    (net (code "45") (name "Net-(U19-COM)") (class "Default")
      (node (ref "R57") (pin "2") (pinfunction "2_2") (pintype "input"))
      (node (ref "U19") (pin "5") (pinfunction "COM_5") (pintype "unspecified"))
    )
    (net (code "46") (name "Net-(U19-CSP)") (class "Default")
      (node (ref "L2") (pin "1") (pinfunction "1_1") (pintype "input"))
      (node (ref "R54") (pin "1") (pinfunction "1_1") (pintype "input"))
      (node (ref "U19") (pin "8") (pinfunction "CSP_8") (pintype "unspecified"))
    )
    (net (code "47") (name "Net-(U19-MPPT)") (class "Default")
      (node (ref "R55") (pin "1") (pinfunction "1_1") (pintype "input"))
      (node (ref "R56") (pin "1") (pinfunction "1_1") (pintype "input"))
      (node (ref "U19") (pin "6") (pinfunction "MPPT_6") (pintype "unspecified"))
    )
    (net (code "48") (name "Net-(U19-VG)") (class "Default")
      (node (ref "C59") (pin "2") (pinfunction "2_2") (pintype "unspecified"))
      (node (ref "U19") (pin "1") (pinfunction "VG_1") (pintype "unspecified"))
    )
    (net (code "49") (name "Net-(USB1-D+)") (class "Default")
      (node (ref "R28") (pin "1") (pinfunction "1_1") (pintype "input"))
      (node (ref "USB1") (pin "3") (pinfunction "D+_3") (pintype "input"))
    )
    (net (code "50") (name "Net-(USB1-D-)") (class "Default")
      (node (ref "R37") (pin "1") (pinfunction "1_1") (pintype "input"))
      (node (ref "USB1") (pin "2") (pinfunction "D-_2") (pintype "input"))
    )
    (net (code "51") (name "SENSE_LDO_EN") (class "Default")
      (node (ref "U24") (pin "3") (pinfunction "EN_3") (pintype "unspecified"))
      (node (ref "U3") (pin "38") (pinfunction "PA15_38") (pintype "unspecified"))
    )
    (net (code "52") (name "SOLAR_IN") (class "Default")
      (node (ref "C59") (pin "1") (pinfunction "1_1") (pintype "unspecified"))
      (node (ref "C66") (pin "2") (pinfunction "2_2") (pintype "unspecified"))
      (node (ref "D10") (pin "1") (pinfunction "K_1") (pintype "unspecified"))
      (node (ref "D9") (pin "1") (pinfunction "K_1") (pintype "unspecified"))
      (node (ref "Q1") (pin "3") (pinfunction "S_3") (pintype "unspecified"))
      (node (ref "R55") (pin "2") (pinfunction "2_2") (pintype "input"))
      (node (ref "U19") (pin "9") (pinfunction "VCC_9") (pintype "unspecified"))
    )
    (net (code "53") (name "VBUS") (class "Default")
      (node (ref "D10") (pin "2") (pinfunction "A_2") (pintype "unspecified"))
      (node (ref "D14") (pin "2") (pinfunction "A_2") (pintype "unspecified"))
      (node (ref "R25") (pin "2") (pinfunction "2_2") (pintype "input"))
      (node (ref "USB1") (pin "1") (pinfunction "VCC_1") (pintype "input"))
    )
    (net (code "54") (name "VCC") (class "Default")
      (node (ref "C10") (pin "2") (pinfunction "2_2") (pintype "unspecified"))
      (node (ref "C11") (pin "2") (pinfunction "2_2") (pintype "unspecified"))
      (node (ref "C34") (pin "1") (pinfunction "1_1") (pintype "unspecified"))
      (node (ref "C35") (pin "1") (pinfunction "1_1") (pintype "unspecified"))
      (node (ref "C36") (pin "1") (pinfunction "1_1") (pintype "unspecified"))
      (node (ref "C37") (pin "1") (pinfunction "1_1") (pintype "unspecified"))
      (node (ref "C38") (pin "1") (pinfunction "1_1") (pintype "unspecified"))
      (node (ref "C39") (pin "1") (pinfunction "1_1") (pintype "unspecified"))
      (node (ref "C40") (pin "2") (pinfunction "2_2") (pintype "unspecified"))
      (node (ref "C49") (pin "1") (pinfunction "1_1") (pintype "unspecified"))
      (node (ref "C50") (pin "2") (pinfunction "2_2") (pintype "unspecified"))
      (node (ref "C51") (pin "2") (pinfunction "2_2") (pintype "unspecified"))
      (node (ref "H1") (pin "5") (pinfunction "5_5") (pintype "unspecified"))
      (node (ref "R29") (pin "2") (pinfunction "2_2") (pintype "input"))
      (node (ref "R40") (pin "2") (pinfunction "2_2") (pintype "input"))
      (node (ref "R41") (pin "1") (pinfunction "1_1") (pintype "input"))
      (node (ref "U10") (pin "5") (pinfunction "VS_5") (pintype "unspecified"))
      (node (ref "U12") (pin "2") (pinfunction "2_2") (pintype "unspecified"))
      (node (ref "U23") (pin "5") (pinfunction "OUT_5") (pintype "unspecified"))
      (node (ref "U3") (pin "1") (pinfunction "VBAT_1") (pintype "unspecified"))
      (node (ref "U3") (pin "24") (pinfunction "VDD_24") (pintype "unspecified"))
      (node (ref "U3") (pin "36") (pinfunction "VDDUSB_36") (pintype "unspecified"))
      (node (ref "U3") (pin "48") (pinfunction "VDD_48") (pintype "unspecified"))
      (node (ref "U3") (pin "9") (pinfunction "VDDA/VREF+_9") (pintype "unspecified"))
      (node (ref "U5") (pin "9") (pinfunction "VCC_9") (pintype "input"))
      (node (ref "U9") (pin "3") (pinfunction "WP#(IO2)_3") (pintype "unspecified"))
      (node (ref "U9") (pin "7") (pinfunction "HOLD#_or_RESET#(IO3)_7") (pintype "unspecified"))
      (node (ref "U9") (pin "8") (pinfunction "VCC_8") (pintype "unspecified"))
    )
    (net (code "55") (name "VCC_BAT_IN") (class "Default")
      (node (ref "BT2") (pin "2") (pinfunction "+_2") (pintype "input"))
      (node (ref "C60") (pin "1") (pinfunction "1_1") (pintype "unspecified"))
      (node (ref "C62") (pin "2") (pinfunction "2_2") (pintype "input"))
      (node (ref "H5") (pin "3") (pinfunction "3_3") (pintype "unspecified"))
      (node (ref "R30") (pin "2") (pinfunction "2_2") (pintype "input"))
      (node (ref "R54") (pin "2") (pinfunction "2_2") (pintype "input"))
      (node (ref "U19") (pin "7") (pinfunction "BAT_7") (pintype "unspecified"))
    )
    (net (code "56") (name "VCC_IN") (class "Default")
      (node (ref "C44") (pin "2") (pinfunction "2_2") (pintype "input"))
      (node (ref "C45") (pin "2") (pinfunction "2_2") (pintype "unspecified"))
      (node (ref "C46") (pin "2") (pinfunction "2_2") (pintype "unspecified"))
      (node (ref "C47") (pin "2") (pinfunction "2_2") (pintype "input"))
      (node (ref "H5") (pin "2") (pinfunction "2_2") (pintype "unspecified"))
      (node (ref "U23") (pin "1") (pinfunction "IN_1") (pintype "unspecified"))
      (node (ref "U23") (pin "3") (pinfunction "EN_3") (pintype "unspecified"))
      (node (ref "U24") (pin "1") (pinfunction "IN_1") (pintype "unspecified"))
    )
    (net (code "57") (name "VCC_SENSE") (class "Default")
      (node (ref "C48") (pin "2") (pinfunction "2_2") (pintype "unspecified"))
      (node (ref "H3") (pin "4") (pinfunction "4_4") (pintype "unspecified"))
      (node (ref "H4") (pin "4") (pinfunction "4_4") (pintype "unspecified"))
      (node (ref "R38") (pin "2") (pinfunction "2_2") (pintype "input"))
      (node (ref "R39") (pin "2") (pinfunction "2_2") (pintype "input"))
      (node (ref "U24") (pin "5") (pinfunction "OUT_5") (pintype "unspecified"))
    )
    (net (code "58") (name "unconnected-(U3-PB15-Pad28)") (class "Default")
      (node (ref "U3") (pin "28") (pinfunction "PB15_28") (pintype "unspecified"))
    )
    (net (code "59") (name "unconnected-(U3-PF0-OSC_IN-Pad5)") (class "Default")
      (node (ref "U3") (pin "5") (pinfunction "PF0-OSC_IN_5") (pintype "unspecified"))
    )
    (net (code "60") (name "unconnected-(U3-PF1-OSC_OUT-Pad6)") (class "Default")
      (node (ref "U3") (pin "6") (pinfunction "PF1-OSC_OUT_6") (pintype "unspecified"))
    )
    (net (code "61") (name "unconnected-(U5-ANT-Pad21)") (class "Default")
      (node (ref "U5") (pin "21") (pinfunction "ANT_21") (pintype "input"))
    )
    (net (code "62") (name "unconnected-(U23-NC-Pad4)") (class "Default")
      (node (ref "U23") (pin "4") (pinfunction "NC_4") (pintype "unspecified"))
    )
    (net (code "63") (name "unconnected-(U24-NC-Pad4)") (class "Default")
      (node (ref "U24") (pin "4") (pinfunction "NC_4") (pintype "unspecified"))
    )
    (net (code "64") (name "unconnected-(USB1-ID-Pad4)") (class "Default")
      (node (ref "USB1") (pin "4") (pinfunction "ID_4") (pintype "input"))
    )
  )
)
